# buggym2017.net
KiCad netlist of a schematic drawn in EAGLE
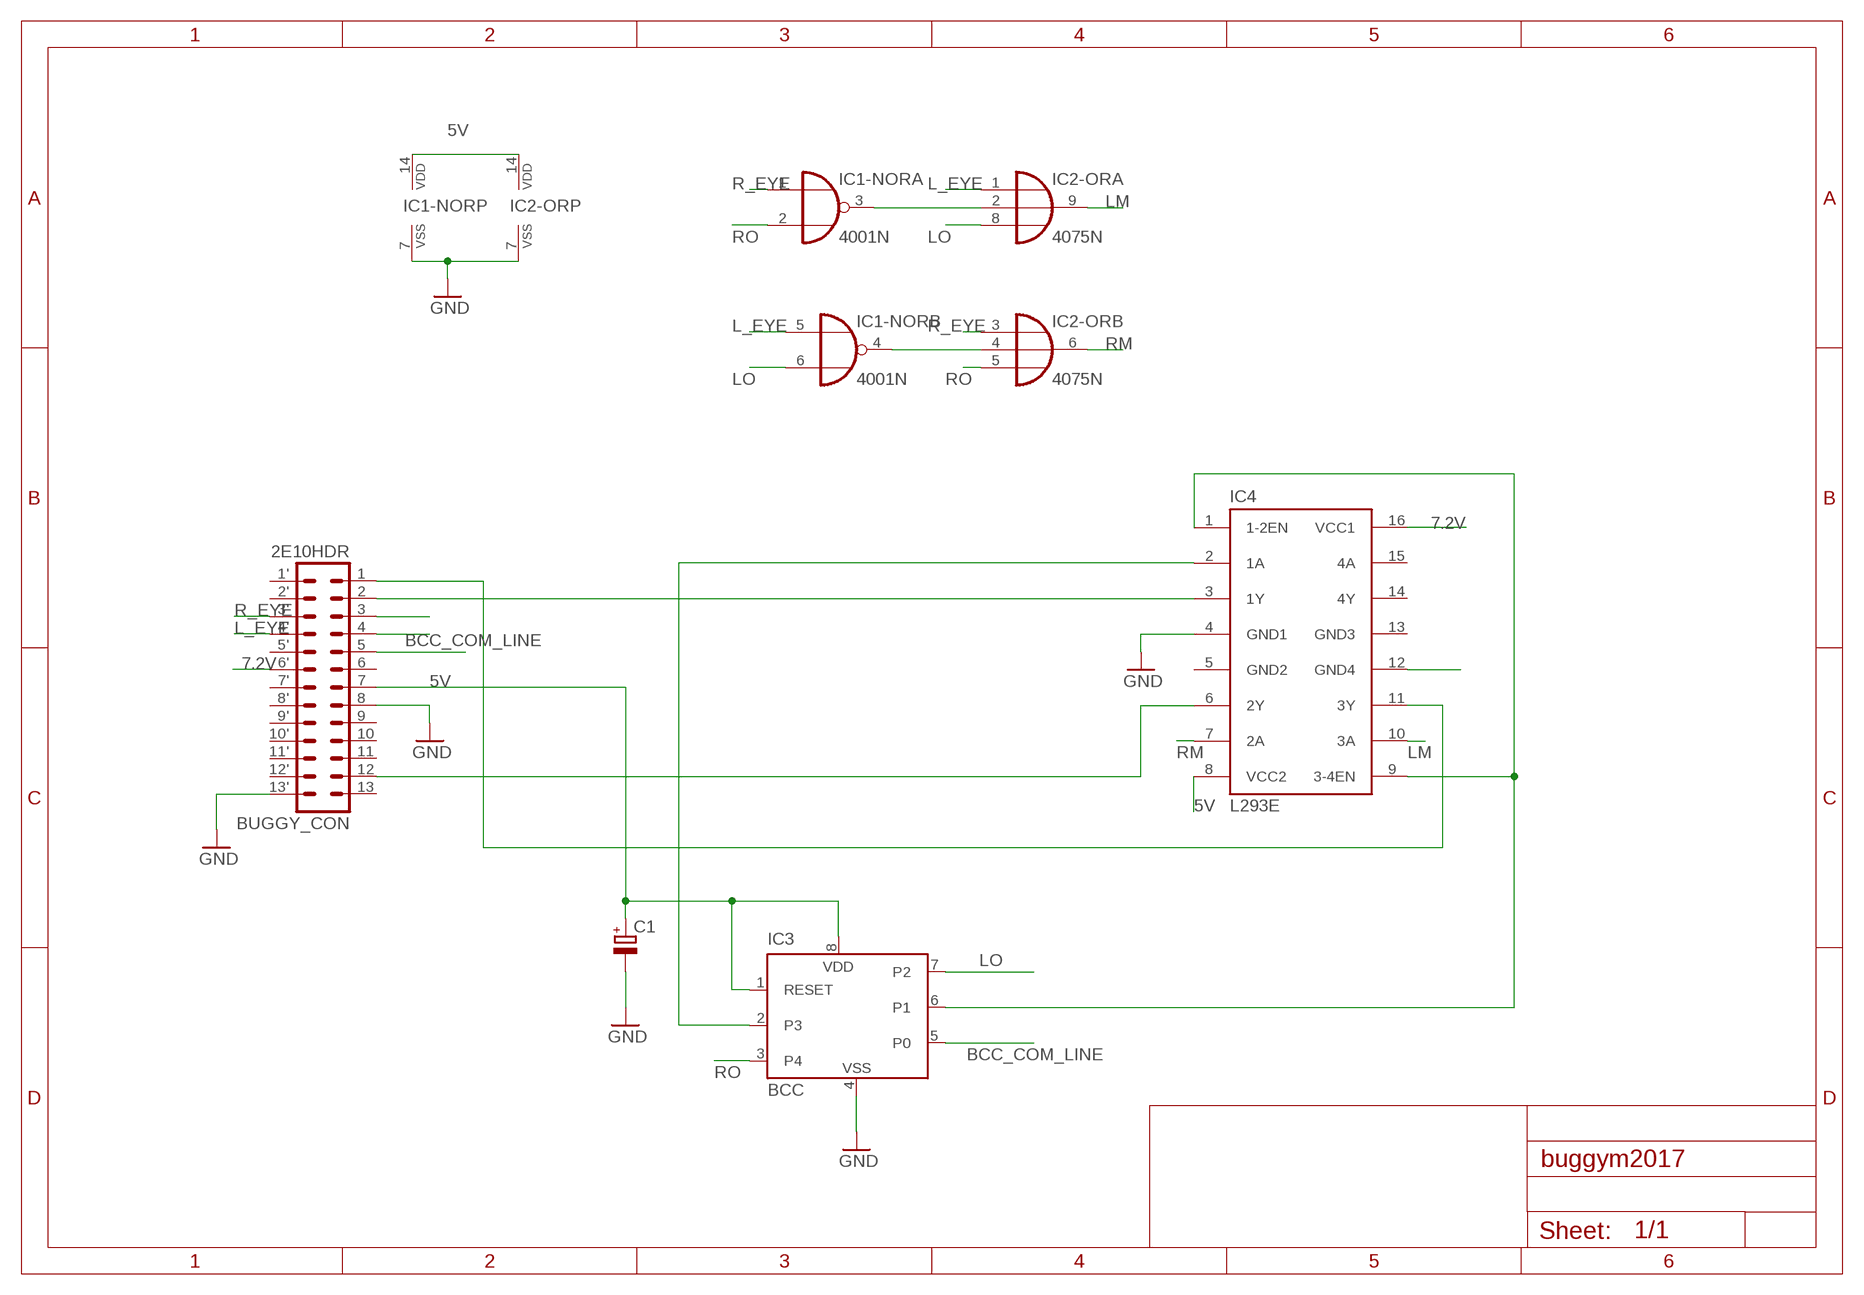
[diagram p0: schematic, sheet 1]

(export (version "E")
  (design (tool "Eeschema 10.0.6"))
  (components
    (comp (ref "BUGGY_CON")
      (value "2E10HDR")
      (footprint "eagle-import:2E10BOARD")
      (libsource (lib "eagle-import") (part "2E10HDR"))
    )
    (comp (ref "C1")
      (value "CPOL-EUE5-4")
      (footprint "eagle-import:E5-4")
      (libsource (lib "eagle-import") (part "CPOL-EUE5-4"))
    )
    (comp (ref "IC1-NOR")
      (value "4001N")
      (footprint "eagle-import:DIL14")
      (libsource (lib "eagle-import") (part "4001N"))
    )
    (comp (ref "IC2-OR")
      (value "4075N")
      (footprint "eagle-import:DIL14")
      (libsource (lib "eagle-import") (part "4075N"))
    )
    (comp (ref "IC3")
      (value "BCC")
      (footprint "eagle-import:DIL8")
      (libsource (lib "eagle-import") (part "BCC"))
    )
    (comp (ref "IC4")
      (value "L293E")
      (footprint "eagle-import:DIL16")
      (fields (field (name "MF") "Arrow Electronics"))
      (libsource (lib "eagle-import") (part "L293E"))
    )
  )
  (nets
    (net (code "1") (name "/5V") (class "Default")
      (node (ref "BUGGY_CON") (pin "7") (pinfunction "7_7") (pintype "passive"))
      (node (ref "C1") (pin "+") (pinfunction "+_+") (pintype "passive"))
      (node (ref "IC1-NOR") (pin "14") (pinfunction "VDD_14") (pintype "power_in"))
      (node (ref "IC2-OR") (pin "14") (pinfunction "VDD_14") (pintype "power_in"))
      (node (ref "IC3") (pin "1") (pinfunction "RESET_1") (pintype "bidirectional"))
      (node (ref "IC3") (pin "8") (pinfunction "5V_8") (pintype "power_in"))
      (node (ref "IC4") (pin "8") (pinfunction "VCC2_8") (pintype "power_in"))
    )
    (net (code "2") (name "/7.2V") (class "Default")
      (node (ref "BUGGY_CON") (pin "6'") (pinfunction "6'_6'") (pintype "passive"))
      (node (ref "IC4") (pin "16") (pinfunction "VCC1_16") (pintype "power_in"))
    )
    (net (code "3") (name "/BCC_COM_LINE") (class "Default")
      (node (ref "BUGGY_CON") (pin "5") (pinfunction "5_5") (pintype "passive"))
      (node (ref "IC3") (pin "5") (pinfunction "P0_5") (pintype "bidirectional"))
    )
    (net (code "4") (name "/GND2") (class "Default")
      (node (ref "IC4") (pin "5") (pinfunction "GND2_5") (pintype "power_in"))
    )
    (net (code "5") (name "/GND3") (class "Default")
      (node (ref "IC4") (pin "13") (pinfunction "GND3_13") (pintype "power_in"))
    )
    (net (code "6") (name "/LM") (class "Default")
      (node (ref "IC2-OR") (pin "9") (pinfunction "O_9") (pintype "output"))
      (node (ref "IC4") (pin "10") (pinfunction "3A_10") (pintype "input"))
    )
    (net (code "7") (name "/LO") (class "Default")
      (node (ref "IC1-NOR") (pin "6") (pinfunction "I1_6") (pintype "input"))
      (node (ref "IC2-OR") (pin "8") (pinfunction "I2_8") (pintype "input"))
      (node (ref "IC3") (pin "7") (pinfunction "P2_7") (pintype "bidirectional"))
    )
    (net (code "8") (name "/L_EYE") (class "Default")
      (node (ref "BUGGY_CON") (pin "4") (pinfunction "4_4") (pintype "passive"))
      (node (ref "BUGGY_CON") (pin "4'") (pinfunction "4'_4'") (pintype "passive"))
      (node (ref "IC1-NOR") (pin "5") (pinfunction "I0_5") (pintype "input"))
      (node (ref "IC2-OR") (pin "1") (pinfunction "I0_1") (pintype "input"))
    )
    (net (code "9") (name "/RM") (class "Default")
      (node (ref "IC2-OR") (pin "6") (pinfunction "O_6") (pintype "output"))
      (node (ref "IC4") (pin "7") (pinfunction "2A_7") (pintype "input"))
    )
    (net (code "10") (name "/RO") (class "Default")
      (node (ref "IC1-NOR") (pin "2") (pinfunction "I1_2") (pintype "input"))
      (node (ref "IC2-OR") (pin "5") (pinfunction "I2_5") (pintype "input"))
      (node (ref "IC3") (pin "3") (pinfunction "P4_3") (pintype "input"))
    )
    (net (code "11") (name "/R_EYE") (class "Default")
      (node (ref "BUGGY_CON") (pin "3") (pinfunction "3_3") (pintype "passive"))
      (node (ref "BUGGY_CON") (pin "3'") (pinfunction "3'_3'") (pintype "passive"))
      (node (ref "IC1-NOR") (pin "1") (pinfunction "I0_1") (pintype "input"))
      (node (ref "IC2-OR") (pin "3") (pinfunction "I0_3") (pintype "input"))
    )
    (net (code "12") (name "GND") (class "Default")
      (node (ref "BUGGY_CON") (pin "13'") (pinfunction "13'_13'") (pintype "passive"))
      (node (ref "BUGGY_CON") (pin "8") (pinfunction "8_8") (pintype "passive"))
      (node (ref "C1") (pin "-") (pinfunction "-_-") (pintype "passive"))
      (node (ref "IC1-NOR") (pin "7") (pinfunction "VSS_7") (pintype "power_in"))
      (node (ref "IC2-OR") (pin "7") (pinfunction "VSS_7") (pintype "power_in"))
      (node (ref "IC3") (pin "4") (pinfunction "VSS_4") (pintype "power_in"))
      (node (ref "IC4") (pin "4") (pinfunction "GND1_4") (pintype "power_in"))
    )
    (net (code "13") (name "Net-(IC1-NORA-O)") (class "Default")
      (node (ref "IC1-NOR") (pin "3") (pinfunction "O_3") (pintype "output"))
      (node (ref "IC2-OR") (pin "2") (pinfunction "I1_2") (pintype "input"))
    )
    (net (code "14") (name "Net-(IC1-NORB-O)") (class "Default")
      (node (ref "IC1-NOR") (pin "4") (pinfunction "O_4") (pintype "output"))
      (node (ref "IC2-OR") (pin "4") (pinfunction "I1_4") (pintype "input"))
    )
    (net (code "15") (name "Net-(IC3-P1)") (class "Default")
      (node (ref "IC3") (pin "6") (pinfunction "P1_6") (pintype "bidirectional"))
      (node (ref "IC4") (pin "1") (pinfunction "1-2EN_1") (pintype "input"))
      (node (ref "IC4") (pin "9") (pinfunction "3-4EN_9") (pintype "input"))
    )
    (net (code "16") (name "Net-(IC3-P3)") (class "Default")
      (node (ref "IC3") (pin "2") (pinfunction "P3_2") (pintype "bidirectional"))
      (node (ref "IC4") (pin "2") (pinfunction "1A_2") (pintype "input"))
    )
    (net (code "17") (name "Net-(IC4-1Y)") (class "Default")
      (node (ref "BUGGY_CON") (pin "2") (pinfunction "2_2") (pintype "passive"))
      (node (ref "IC4") (pin "3") (pinfunction "1Y_3") (pintype "output"))
    )
    (net (code "18") (name "Net-(IC4-2Y)") (class "Default")
      (node (ref "BUGGY_CON") (pin "12") (pinfunction "12_12") (pintype "passive"))
      (node (ref "IC4") (pin "6") (pinfunction "2Y_6") (pintype "output"))
    )
    (net (code "19") (name "Net-(IC4-3Y)") (class "Default")
      (node (ref "BUGGY_CON") (pin "1") (pinfunction "1_1") (pintype "passive"))
      (node (ref "IC4") (pin "11") (pinfunction "3Y_11") (pintype "output"))
    )
    (net (code "20") (name "unconnected-(BUGGY_CON-Pad1')") (class "Default")
      (node (ref "BUGGY_CON") (pin "1'") (pinfunction "1'_1'") (pintype "passive"))
    )
    (net (code "21") (name "unconnected-(BUGGY_CON-Pad2')") (class "Default")
      (node (ref "BUGGY_CON") (pin "2'") (pinfunction "2'_2'") (pintype "passive"))
    )
    (net (code "22") (name "unconnected-(BUGGY_CON-Pad5')") (class "Default")
      (node (ref "BUGGY_CON") (pin "5'") (pinfunction "5'_5'") (pintype "passive"))
    )
    (net (code "23") (name "unconnected-(BUGGY_CON-Pad6)") (class "Default")
      (node (ref "BUGGY_CON") (pin "6") (pinfunction "6_6") (pintype "passive"))
    )
    (net (code "24") (name "unconnected-(BUGGY_CON-Pad7')") (class "Default")
      (node (ref "BUGGY_CON") (pin "7'") (pinfunction "7'_7'") (pintype "passive"))
    )
    (net (code "25") (name "unconnected-(BUGGY_CON-Pad8')") (class "Default")
      (node (ref "BUGGY_CON") (pin "8'") (pinfunction "8'_8'") (pintype "passive"))
    )
    (net (code "26") (name "unconnected-(BUGGY_CON-Pad9')") (class "Default")
      (node (ref "BUGGY_CON") (pin "9'") (pinfunction "9'_9'") (pintype "passive"))
    )
    (net (code "27") (name "unconnected-(BUGGY_CON-Pad9)") (class "Default")
      (node (ref "BUGGY_CON") (pin "9") (pinfunction "9_9") (pintype "passive"))
    )
    (net (code "28") (name "unconnected-(BUGGY_CON-Pad10')") (class "Default")
      (node (ref "BUGGY_CON") (pin "10'") (pinfunction "10'_10'") (pintype "passive"))
    )
    (net (code "29") (name "unconnected-(BUGGY_CON-Pad10)") (class "Default")
      (node (ref "BUGGY_CON") (pin "10") (pinfunction "10_10") (pintype "passive"))
    )
    (net (code "30") (name "unconnected-(BUGGY_CON-Pad11')") (class "Default")
      (node (ref "BUGGY_CON") (pin "11'") (pinfunction "11'_11'") (pintype "passive"))
    )
    (net (code "31") (name "unconnected-(BUGGY_CON-Pad11)") (class "Default")
      (node (ref "BUGGY_CON") (pin "11") (pinfunction "11_11") (pintype "passive"))
    )
    (net (code "32") (name "unconnected-(BUGGY_CON-Pad12')") (class "Default")
      (node (ref "BUGGY_CON") (pin "12'") (pinfunction "12'_12'") (pintype "passive"))
    )
    (net (code "33") (name "unconnected-(BUGGY_CON-Pad13)") (class "Default")
      (node (ref "BUGGY_CON") (pin "13") (pinfunction "13_13") (pintype "passive"))
    )
    (net (code "34") (name "unconnected-(IC4-4A-Pad15)") (class "Default")
      (node (ref "IC4") (pin "15") (pinfunction "4A_15") (pintype "input"))
    )
    (net (code "35") (name "unconnected-(IC4-4Y-Pad14)") (class "Default")
      (node (ref "IC4") (pin "14") (pinfunction "4Y_14") (pintype "output"))
    )
    (net (code "36") (name "unconnected-(IC4-GND4-Pad12)") (class "Default")
      (node (ref "IC4") (pin "12") (pinfunction "GND4_12") (pintype "power_in"))
    )
  )
)
